# OxFloodNet_sensor.net
KiCad netlist of a schematic drawn in EAGLE
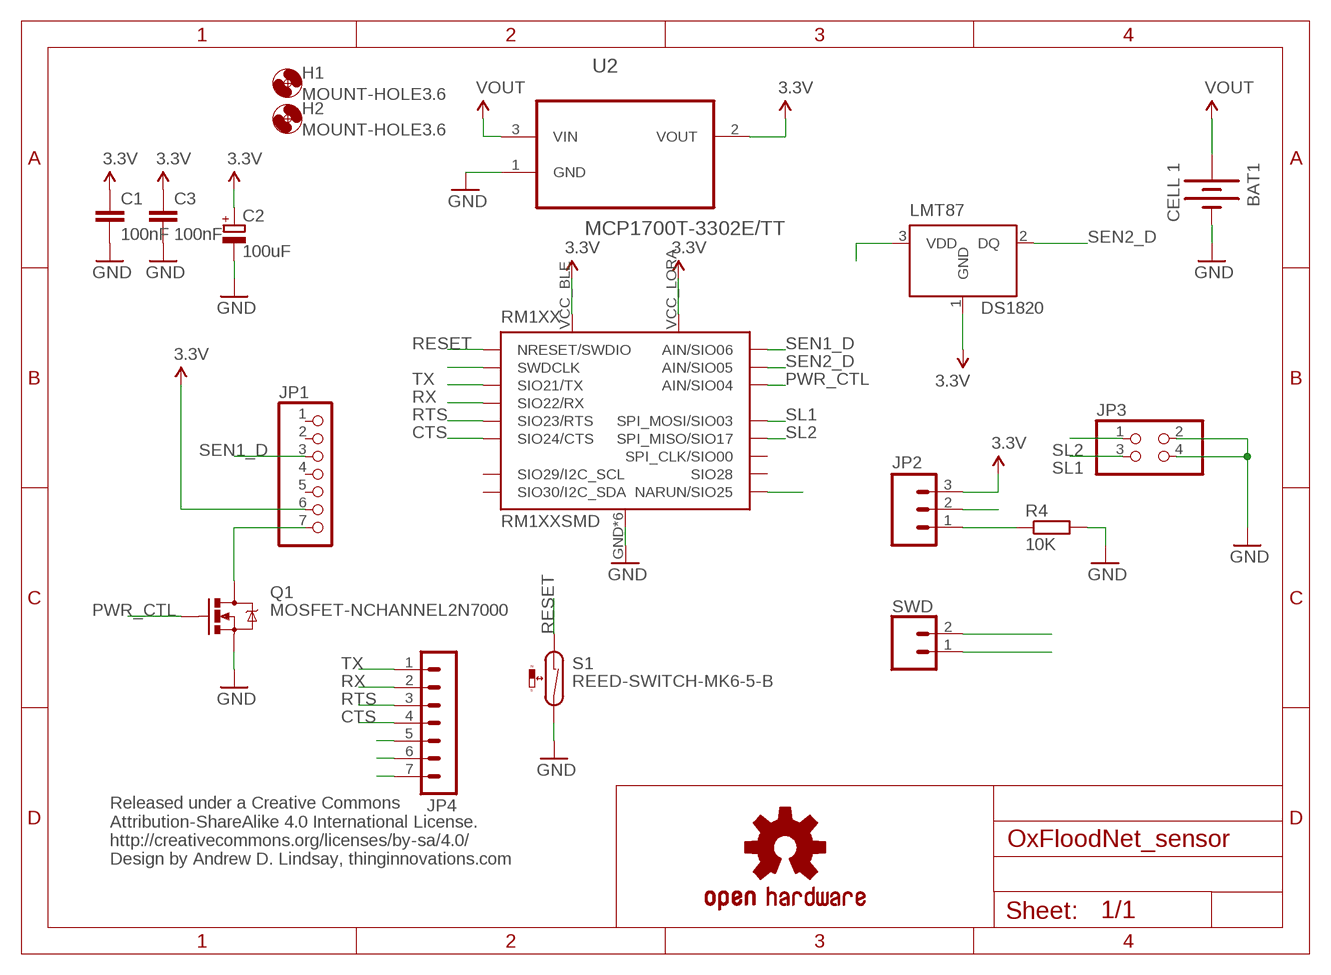
[diagram p0: schematic, sheet 1]

(export (version "E")
  (design (tool "Eeschema 10.0.6"))
  (components
    (comp (ref "BAT1")
      (value "CELL 1")
      (footprint "eagle-import:BATTERY-AA")
      (libsource (lib "eagle-import") (part "BATTERYAA"))
    )
    (comp (ref "C1")
      (value "100nF")
      (footprint "eagle-import:C025-024X044")
      (libsource (lib "eagle-import") (part "C-EU025-024X044"))
    )
    (comp (ref "C2")
      (value "100uF")
      (footprint "eagle-import:E2,5-6E")
      (libsource (lib "eagle-import") (part "CPOL-EUE2,5-6E"))
    )
    (comp (ref "C3")
      (value "100nF")
      (footprint "eagle-import:C025-024X044")
      (libsource (lib "eagle-import") (part "C-EU025-024X044"))
    )
    (comp (ref "H1")
      (value "MOUNT-HOLE3.6")
      (footprint "eagle-import:3,6")
      (libsource (lib "eagle-import") (part "MOUNT-HOLE3.6"))
    )
    (comp (ref "H2")
      (value "MOUNT-HOLE3.6")
      (footprint "eagle-import:3,6")
      (libsource (lib "eagle-import") (part "MOUNT-HOLE3.6"))
    )
    (comp (ref "JP1")
      (value "1X07")
      (footprint "eagle-import:1X07")
      (libsource (lib "eagle-import") (part "1X07"))
    )
    (comp (ref "JP2")
      (value "M03PTH")
      (footprint "eagle-import:1X03")
      (libsource (lib "eagle-import") (part "M03PTH"))
    )
    (comp (ref "JP3")
      (value "2X02")
      (footprint "eagle-import:2X02")
      (libsource (lib "eagle-import") (part "2X02"))
    )
    (comp (ref "JP4")
      (value "MA07-1")
      (footprint "eagle-import:MA07-1")
      (libsource (lib "eagle-import") (part "MA07-1"))
    )
    (comp (ref "LMT87")
      (value "DS1820")
      (footprint "eagle-import:TO-92")
      (libsource (lib "eagle-import") (part "DS1820"))
    )
    (comp (ref "LOGO1")
      (value "OSHW-LOGOM")
      (footprint "eagle-import:OSHW-LOGO-M")
      (libsource (lib "eagle-import") (part "OSHW-LOGOM"))
    )
    (comp (ref "Q1")
      (value "MOSFET-NCHANNEL2N7000")
      (footprint "eagle-import:TO-92")
      (libsource (lib "eagle-import") (part "MOSFET-NCHANNEL2N7000"))
    )
    (comp (ref "R4")
      (value "10K")
      (footprint "eagle-import:R0603")
      (libsource (lib "eagle-import") (part "R-EU_R0603"))
    )
    (comp (ref "RM1XX")
      (value "RM1XXSMD")
      (footprint "eagle-import:RM1XX")
      (libsource (lib "eagle-import") (part "RM1XXSMD"))
    )
    (comp (ref "S1")
      (value "REED-SWITCH-MK6-5-B")
      (footprint "eagle-import:MK6-5")
      (fields (field (name "MF") "MEDER") (field (name "MPN") "MK6-5-B"))
      (libsource (lib "eagle-import") (part "REED-SWITCH-MK6-5-B"))
    )
    (comp (ref "SWD")
      (value "CONN_02")
      (footprint "eagle-import:1X02")
      (libsource (lib "eagle-import") (part "CONN_02"))
    )
    (comp (ref "U2")
      (value "MCP1700T-3302E/TT")
      (footprint "eagle-import:SOT95P237X112-3N")
      (libsource (lib "eagle-import") (part "MCP1700T-3302E/TT"))
    )
  )
  (nets
    (net (code "1") (name "/ARUN") (class "Default")
      (node (ref "JP2") (pin "2") (pinfunction "2_2") (pintype "passive"))
      (node (ref "RM1XX") (pin "SIO25") (pinfunction "NARUN/SIO25_SIO25") (pintype "bidirectional"))
    )
    (net (code "2") (name "/CTS") (class "Default")
      (node (ref "JP4") (pin "4") (pinfunction "4_4") (pintype "passive"))
      (node (ref "RM1XX") (pin "SIO24") (pinfunction "SIO24/CTS_SIO24") (pintype "bidirectional"))
    )
    (net (code "3") (name "/N$2") (class "Default")
      (node (ref "JP1") (pin "7") (pinfunction "7_7") (pintype "passive"))
      (node (ref "LMT87") (pin "3") (pinfunction "VDD_3") (pintype "input"))
      (node (ref "Q1") (pin "3") (pinfunction "D_3") (pintype "passive"))
    )
    (net (code "4") (name "/PWR_CTL") (class "Default")
      (node (ref "Q1") (pin "2") (pinfunction "G_2") (pintype "passive"))
      (node (ref "RM1XX") (pin "SIO04") (pinfunction "AIN/SIO04_SIO04") (pintype "bidirectional"))
    )
    (net (code "5") (name "/RESET") (class "Default")
      (node (ref "RM1XX") (pin "RESET") (pinfunction "NRESET/SWDIO_RESET") (pintype "input"))
      (node (ref "S1") (pin "1") (pinfunction "1_1") (pintype "passive"))
      (node (ref "SWD") (pin "2") (pinfunction "2_2") (pintype "passive"))
    )
    (net (code "6") (name "/RTS") (class "Default")
      (node (ref "JP4") (pin "3") (pinfunction "3_3") (pintype "passive"))
      (node (ref "RM1XX") (pin "SIO23") (pinfunction "SIO23/RTS_SIO23") (pintype "bidirectional"))
    )
    (net (code "7") (name "/RX") (class "Default")
      (node (ref "JP4") (pin "2") (pinfunction "2_2") (pintype "passive"))
      (node (ref "RM1XX") (pin "SIO22") (pinfunction "SIO22/RX_SIO22") (pintype "bidirectional"))
    )
    (net (code "8") (name "/SEN1_D") (class "Default")
      (node (ref "JP1") (pin "3") (pinfunction "3_3") (pintype "passive"))
      (node (ref "RM1XX") (pin "SIO06") (pinfunction "AIN/SIO06_SIO06") (pintype "bidirectional"))
    )
    (net (code "9") (name "/SEN2_D") (class "Default")
      (node (ref "LMT87") (pin "2") (pinfunction "DQ_2") (pintype "output"))
      (node (ref "RM1XX") (pin "SIO05") (pinfunction "AIN/SIO05_SIO05") (pintype "bidirectional"))
    )
    (net (code "10") (name "/SL1") (class "Default")
      (node (ref "JP3") (pin "3") (pinfunction "3_3") (pintype "passive"))
      (node (ref "RM1XX") (pin "SIO03") (pinfunction "SPI_MOSI/SIO03_SIO03") (pintype "bidirectional"))
    )
    (net (code "11") (name "/SL2") (class "Default")
      (node (ref "JP3") (pin "1") (pinfunction "1_1") (pintype "passive"))
      (node (ref "RM1XX") (pin "SIO17") (pinfunction "SPI_MISO/SIO17_SIO17") (pintype "bidirectional"))
    )
    (net (code "12") (name "/SWDCLK") (class "Default")
      (node (ref "RM1XX") (pin "SWDCLK") (pinfunction "SWDCLK_SWDCLK") (pintype "input"))
      (node (ref "SWD") (pin "1") (pinfunction "1_1") (pintype "passive"))
    )
    (net (code "13") (name "/TX") (class "Default")
      (node (ref "JP4") (pin "1") (pinfunction "1_1") (pintype "passive"))
      (node (ref "RM1XX") (pin "SIO21") (pinfunction "SIO21/TX_SIO21") (pintype "bidirectional"))
    )
    (net (code "14") (name "3.3V") (class "Default")
      (node (ref "C1") (pin "1") (pinfunction "1_1") (pintype "passive"))
      (node (ref "C2") (pin "+") (pinfunction "+_+") (pintype "passive"))
      (node (ref "C3") (pin "1") (pinfunction "1_1") (pintype "passive"))
      (node (ref "JP1") (pin "6") (pinfunction "6_6") (pintype "passive"))
      (node (ref "JP2") (pin "3") (pinfunction "3_3") (pintype "passive"))
      (node (ref "JP4") (pin "6") (pinfunction "6_6") (pintype "passive"))
      (node (ref "LMT87") (pin "1") (pinfunction "GND_1") (pintype "power_in"))
      (node (ref "RM1XX") (pin "VCC_BLE") (pinfunction "VCC_BLE_VCC_BLE") (pintype "power_in"))
      (node (ref "RM1XX") (pin "VCC_LORA") (pinfunction "VCC_LORA_VCC_LORA") (pintype "power_in"))
      (node (ref "U2") (pin "2") (pinfunction "VOUT_2") (pintype "output"))
    )
    (net (code "15") (name "GND") (class "Default")
      (node (ref "BAT1") (pin "GND@1") (pinfunction "-_GND@1") (pintype "power_in"))
      (node (ref "C1") (pin "2") (pinfunction "2_2") (pintype "passive"))
      (node (ref "C2") (pin "-") (pinfunction "-_-") (pintype "passive"))
      (node (ref "C3") (pin "2") (pinfunction "2_2") (pintype "passive"))
      (node (ref "JP3") (pin "2") (pinfunction "2_2") (pintype "passive"))
      (node (ref "JP3") (pin "4") (pinfunction "4_4") (pintype "passive"))
      (node (ref "JP4") (pin "5") (pinfunction "5_5") (pintype "passive"))
      (node (ref "Q1") (pin "1") (pinfunction "S_1") (pintype "passive"))
      (node (ref "R4") (pin "2") (pinfunction "2_2") (pintype "passive"))
      (node (ref "RM1XX") (pin "GND") (pinfunction "GND_GND") (pintype "power_in"))
      (node (ref "RM1XX") (pin "GND1") (pinfunction "GND_GND1") (pintype "power_in"))
      (node (ref "RM1XX") (pin "GND2") (pinfunction "GND_GND2") (pintype "power_in"))
      (node (ref "RM1XX") (pin "GND3") (pinfunction "GND_GND3") (pintype "power_in"))
      (node (ref "RM1XX") (pin "GND4") (pinfunction "GND_GND4") (pintype "power_in"))
      (node (ref "RM1XX") (pin "GND5") (pinfunction "GND_GND5") (pintype "power_in"))
      (node (ref "S1") (pin "2") (pinfunction "2_2") (pintype "passive"))
      (node (ref "U2") (pin "1") (pinfunction "GND_1") (pintype "passive"))
    )
    (net (code "16") (name "Net-(JP2-Pad1)") (class "Default")
      (node (ref "JP2") (pin "1") (pinfunction "1_1") (pintype "passive"))
      (node (ref "R4") (pin "1") (pinfunction "1_1") (pintype "passive"))
    )
    (net (code "17") (name "VOUT") (class "Default")
      (node (ref "BAT1") (pin "PWR@1") (pinfunction "+_PWR@1") (pintype "power_in"))
      (node (ref "JP4") (pin "7") (pinfunction "7_7") (pintype "passive"))
      (node (ref "U2") (pin "3") (pinfunction "VIN_3") (pintype "input"))
    )
    (net (code "18") (name "unconnected-(JP1-Pad1)") (class "Default")
      (node (ref "JP1") (pin "1") (pinfunction "1_1") (pintype "passive"))
    )
    (net (code "19") (name "unconnected-(JP1-Pad2)") (class "Default")
      (node (ref "JP1") (pin "2") (pinfunction "2_2") (pintype "passive"))
    )
    (net (code "20") (name "unconnected-(JP1-Pad4)") (class "Default")
      (node (ref "JP1") (pin "4") (pinfunction "4_4") (pintype "passive"))
    )
    (net (code "21") (name "unconnected-(JP1-Pad5)") (class "Default")
      (node (ref "JP1") (pin "5") (pinfunction "5_5") (pintype "passive"))
    )
    (net (code "22") (name "unconnected-(RM1XX-PadSIO28)") (class "Default")
      (node (ref "RM1XX") (pin "SIO28") (pinfunction "SIO28_SIO28") (pintype "bidirectional"))
    )
    (net (code "23") (name "unconnected-(RM1XX-SIO29{slash}I2C_SCL-PadSIO29)") (class "Default")
      (node (ref "RM1XX") (pin "SIO29") (pinfunction "SIO29/I2C_SCL_SIO29") (pintype "bidirectional"))
    )
    (net (code "24") (name "unconnected-(RM1XX-SIO30{slash}I2C_SDA-PadSIO30)") (class "Default")
      (node (ref "RM1XX") (pin "SIO30") (pinfunction "SIO30/I2C_SDA_SIO30") (pintype "bidirectional"))
    )
    (net (code "25") (name "unconnected-(RM1XX-SPI_CLK{slash}SIO00-PadSIO00)") (class "Default")
      (node (ref "RM1XX") (pin "SIO00") (pinfunction "SPI_CLK/SIO00_SIO00") (pintype "bidirectional"))
    )
  )
)
